# DfMUX_DAC.net
KiCad netlist of a schematic drawn in Altium Designer
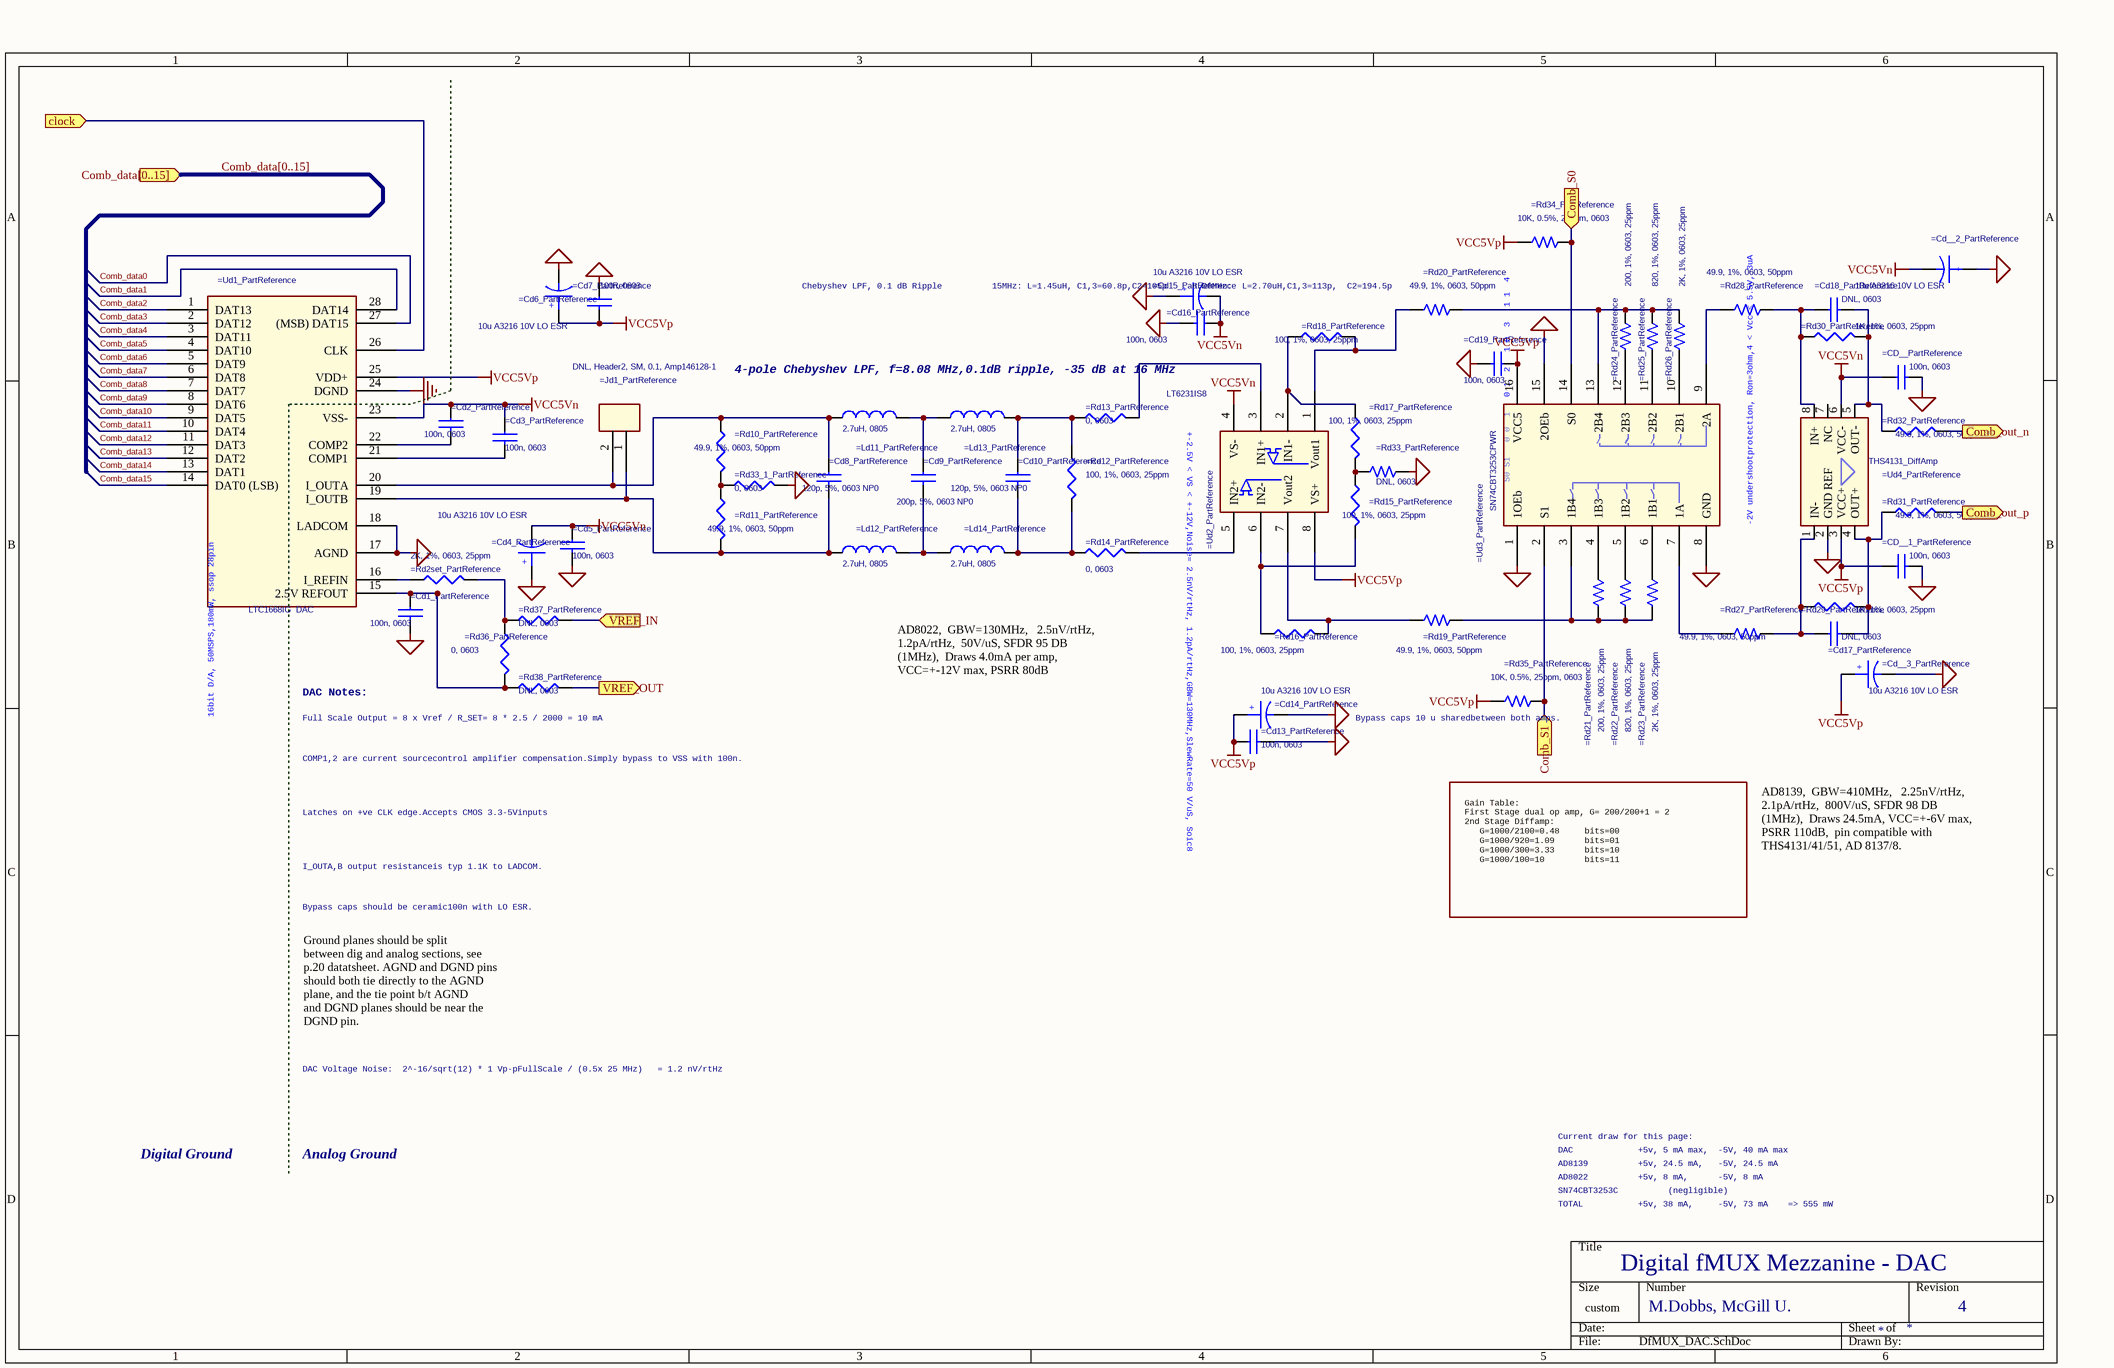
[diagram p0: DfMUX_DAC.SchDoc]

(export (version "E")
  (design (tool "Eeschema 10.0.6"))
  (components
    (comp (ref "=Cd1_PartReference")
      (value "100n, 0603")
      (footprint "0603C")
      (libsource (lib "*") (part "CAPACITOR NON-POL"))
    )
    (comp (ref "=Cd2_PartReference")
      (value "100n, 0603")
      (footprint "0603C")
      (libsource (lib "*") (part "CAPACITOR NON-POL"))
    )
    (comp (ref "=Cd3_PartReference")
      (value "100n, 0603")
      (footprint "0603C")
      (libsource (lib "*") (part "CAPACITOR NON-POL"))
    )
    (comp (ref "=Cd4_PartReference")
      (value "10u A3216 10V LO ESR")
      (libsource (lib "*") (part "CAPACITOR POL"))
    )
    (comp (ref "=Cd5_PartReference")
      (value "100n, 0603")
      (footprint "0603C")
      (libsource (lib "*") (part "CAPACITOR NON-POL"))
    )
    (comp (ref "=Cd6_PartReference")
      (value "10u A3216 10V LO ESR")
      (libsource (lib "*") (part "CAPACITOR POL"))
    )
    (comp (ref "=Cd7_PartReference")
      (value "100n, 0603")
      (footprint "0603C")
      (libsource (lib "*") (part "CAPACITOR NON-POL"))
    )
    (comp (ref "=Cd8_PartReference")
      (value "120p, 5%, 0603 NP0")
      (footprint "0603C")
      (libsource (lib "*") (part "CAPACITOR NON-POL"))
    )
    (comp (ref "=Cd9_PartReference")
      (value "200p, 5%, 0603 NP0")
      (footprint "0603C")
      (libsource (lib "*") (part "CAPACITOR NON-POL"))
    )
    (comp (ref "=Cd10_PartReference")
      (value "120p, 5%, 0603 NP0")
      (footprint "0603C")
      (libsource (lib "*") (part "CAPACITOR NON-POL"))
    )
    (comp (ref "=Cd13_PartReference")
      (value "100n, 0603")
      (footprint "0603C")
      (libsource (lib "*") (part "CAPACITOR NON-POL"))
    )
    (comp (ref "=Cd14_PartReference")
      (value "10u A3216 10V LO ESR")
      (libsource (lib "*") (part "CAPACITOR POL"))
    )
    (comp (ref "=Cd15_PartReference")
      (value "10u A3216 10V LO ESR")
      (libsource (lib "*") (part "CAPACITOR POL"))
    )
    (comp (ref "=Cd16_PartReference")
      (value "100n, 0603")
      (footprint "0603C")
      (libsource (lib "*") (part "CAPACITOR NON-POL"))
    )
    (comp (ref "=Cd17_PartReference")
      (value "DNL, 0603")
      (footprint "0603C")
      (libsource (lib "*") (part "CAPACITOR NON-POL"))
    )
    (comp (ref "=Cd18_PartReference")
      (value "DNL, 0603")
      (footprint "0603C")
      (libsource (lib "*") (part "CAPACITOR NON-POL"))
    )
    (comp (ref "=Cd19_PartReference")
      (value "100n, 0603")
      (footprint "0603C")
      (libsource (lib "*") (part "CAPACITOR NON-POL"))
    )
    (comp (ref "=CD__1_PartReference")
      (value "100n, 0603")
      (footprint "0603C")
      (libsource (lib "*") (part "CAPACITOR NON-POL"))
    )
    (comp (ref "=Cd__2_PartReference")
      (value "10u A3216 10V LO ESR")
      (libsource (lib "") (part "CAPACITOR POL_1"))
    )
    (comp (ref "=Cd__3_PartReference")
      (value "10u A3216 10V LO ESR")
      (libsource (lib "*") (part "CAPACITOR POL"))
    )
    (comp (ref "=CD__PartReference")
      (value "100n, 0603")
      (footprint "0603C")
      (libsource (lib "*") (part "CAPACITOR NON-POL"))
    )
    (comp (ref "=Jd1_PartReference")
      (value "DNL, Header2, SM, 0.1, Amp146128-1")
      (libsource (lib "*") (part "CONN_TRBLK_2"))
    )
    (comp (ref "=Ld11_PartReference") (value "2.7uH, 0805") (libsource (lib "*") (part "INDUCTOR/SM")))
    (comp (ref "=Ld12_PartReference") (value "2.7uH, 0805") (libsource (lib "*") (part "INDUCTOR/SM")))
    (comp (ref "=Ld13_PartReference") (value "2.7uH, 0805") (libsource (lib "*") (part "INDUCTOR/SM")))
    (comp (ref "=Ld14_PartReference") (value "2.7uH, 0805") (libsource (lib "*") (part "INDUCTOR/SM")))
    (comp (ref "=Rd2set_PartReference")
      (value "2K, 1%, 0603, 25ppm")
      (footprint "0603R")
      (libsource (lib "*") (part "R_Dup1"))
    )
    (comp (ref "=Rd10_PartReference")
      (value "49.9, 1%, 0603, 50ppm")
      (footprint "0603R")
      (libsource (lib "*") (part "R_Dup1"))
    )
    (comp (ref "=Rd11_PartReference")
      (value "49.9, 1%, 0603, 50ppm")
      (footprint "0603R")
      (libsource (lib "*") (part "R_Dup1"))
    )
    (comp (ref "=Rd12_PartReference")
      (value "100, 1%, 0603, 25ppm")
      (footprint "0603R")
      (libsource (lib "*") (part "R_Dup1"))
    )
    (comp (ref "=Rd13_PartReference")
      (value "0, 0603")
      (footprint "0603R")
      (libsource (lib "*") (part "R_Dup1"))
    )
    (comp (ref "=Rd14_PartReference")
      (value "0, 0603")
      (footprint "0603R")
      (libsource (lib "*") (part "R_Dup1"))
    )
    (comp (ref "=Rd15_PartReference")
      (value "100, 1%, 0603, 25ppm")
      (footprint "0603R")
      (libsource (lib "*") (part "R_Dup1"))
    )
    (comp (ref "=Rd16_PartReference")
      (value "100, 1%, 0603, 25ppm")
      (footprint "0603R")
      (libsource (lib "*") (part "R_Dup1"))
    )
    (comp (ref "=Rd17_PartReference")
      (value "100, 1%, 0603, 25ppm")
      (footprint "0603R")
      (libsource (lib "*") (part "R_Dup1"))
    )
    (comp (ref "=Rd18_PartReference")
      (value "100, 1%, 0603, 25ppm")
      (footprint "0603R")
      (libsource (lib "*") (part "R_Dup1"))
    )
    (comp (ref "=Rd19_PartReference")
      (value "49.9, 1%, 0603, 50ppm")
      (footprint "0603R")
      (libsource (lib "*") (part "R_Dup2"))
    )
    (comp (ref "=Rd20_PartReference")
      (value "49.9, 1%, 0603, 50ppm")
      (footprint "0603R")
      (libsource (lib "*") (part "R_Dup2"))
    )
    (comp (ref "=Rd21_PartReference")
      (value "200, 1%, 0603, 25ppm")
      (footprint "0603R")
      (libsource (lib "*") (part "R_Dup2"))
    )
    (comp (ref "=Rd22_PartReference")
      (value "820, 1%, 0603, 25ppm")
      (footprint "0603R")
      (libsource (lib "*") (part "R_Dup2"))
    )
    (comp (ref "=Rd23_PartReference")
      (value "2K, 1%, 0603, 25ppm")
      (footprint "0603R")
      (libsource (lib "*") (part "R_Dup2"))
    )
    (comp (ref "=Rd24_PartReference")
      (value "200, 1%, 0603, 25ppm")
      (footprint "0603R")
      (libsource (lib "*") (part "R_Dup2"))
    )
    (comp (ref "=Rd25_PartReference")
      (value "820, 1%, 0603, 25ppm")
      (footprint "0603R")
      (libsource (lib "*") (part "R_Dup2"))
    )
    (comp (ref "=Rd26_PartReference")
      (value "2K, 1%, 0603, 25ppm")
      (footprint "0603R")
      (libsource (lib "*") (part "R_Dup2"))
    )
    (comp (ref "=Rd27_PartReference")
      (value "49.9, 1%, 0603, 50ppm")
      (footprint "0603R")
      (libsource (lib "*") (part "R_Dup2"))
    )
    (comp (ref "=Rd28_PartReference")
      (value "49.9, 1%, 0603, 50ppm")
      (footprint "0603R")
      (libsource (lib "*") (part "R_Dup2"))
    )
    (comp (ref "=Rd29_PartReference")
      (value "1K, 1%, 0603, 25ppm")
      (footprint "0603R")
      (libsource (lib "*") (part "R_Dup1"))
    )
    (comp (ref "=Rd30_PartReference")
      (value "1K, 1%, 0603, 25ppm")
      (footprint "0603R")
      (libsource (lib "*") (part "R_Dup1"))
    )
    (comp (ref "=Rd31_PartReference")
      (value "49.9, 1%, 0603, 50ppm")
      (footprint "0603R")
      (libsource (lib "*") (part "R_Dup1"))
    )
    (comp (ref "=Rd32_PartReference")
      (value "49.9, 1%, 0603, 50ppm")
      (footprint "0603R")
      (libsource (lib "*") (part "R_Dup1"))
    )
    (comp (ref "=Rd33_1_PartReference")
      (value "0, 0603")
      (footprint "0603R")
      (libsource (lib "*") (part "R_Dup1"))
    )
    (comp (ref "=Rd33_PartReference")
      (value "DNL, 0603")
      (footprint "0603R")
      (libsource (lib "*") (part "R_Dup2"))
    )
    (comp (ref "=Rd34_PartReference")
      (value "10K, 0.5%, 25ppm, 0603")
      (footprint "0603R")
      (libsource (lib "*") (part "R_Dup2"))
    )
    (comp (ref "=Rd35_PartReference")
      (value "10K, 0.5%, 25ppm, 0603")
      (footprint "0603R")
      (libsource (lib "*") (part "R_Dup2"))
    )
    (comp (ref "=Rd36_PartReference")
      (value "0, 0603")
      (footprint "0603R")
      (libsource (lib "*") (part "R_Dup1"))
    )
    (comp (ref "=Rd37_PartReference")
      (value "DNL, 0603")
      (footprint "0603R")
      (libsource (lib "*") (part "R_Dup1"))
    )
    (comp (ref "=Rd38_PartReference")
      (value "DNL, 0603")
      (footprint "0603R")
      (libsource (lib "*") (part "R_Dup1"))
    )
    (comp (ref "=Ud1_PartReference") (value "LTC1668IG  DAC") (libsource (lib "*") (part "LTC1668IG  DAC")))
    (comp (ref "=Ud2_PartReference") (value "LT6231IS8") (libsource (lib "*") (part "AD8022AR_0")))
    (comp (ref "=Ud3_PartReference")
      (value "SN74CBT3253CPWR")
      (libsource (lib "*") (part "SN74CBT3253C 4MUX"))
    )
    (comp (ref "=Ud4_PartReference")
      (value "THS4131_DiffAmp")
      (libsource (lib "*") (part "THS4131_DiffAmp_0"))
    )
  )
  (nets
    (net (code "1") (name "/Comb_S0") (class "Default")
      (node (ref "=Rd34_PartReference") (pin "2") (pinfunction "2_2") (pintype "passive"))
      (node (ref "=Ud3_PartReference") (pin "14") (pinfunction "S0_14") (pintype "passive"))
    )
    (net (code "2") (name "/Comb_S1") (class "Default")
      (node (ref "=Rd35_PartReference") (pin "2") (pinfunction "2_2") (pintype "passive"))
      (node (ref "=Ud3_PartReference") (pin "2") (pinfunction "S1_2") (pintype "passive"))
    )
    (net (code "3") (name "/Comb_data0") (class "Default")
      (node (ref "=Ud1_PartReference") (pin "27") (pinfunction "(MSB)_DAT15_27") (pintype "passive"))
    )
    (net (code "4") (name "/Comb_data1") (class "Default")
      (node (ref "=Ud1_PartReference") (pin "28") (pinfunction "DAT14_28") (pintype "passive"))
    )
    (net (code "5") (name "/Comb_data2") (class "Default")
      (node (ref "=Ud1_PartReference") (pin "1") (pinfunction "DAT13_1") (pintype "passive"))
    )
    (net (code "6") (name "/Comb_data3") (class "Default")
      (node (ref "=Ud1_PartReference") (pin "2") (pinfunction "DAT12_2") (pintype "passive"))
    )
    (net (code "7") (name "/Comb_data4") (class "Default")
      (node (ref "=Ud1_PartReference") (pin "3") (pinfunction "DAT11_3") (pintype "passive"))
    )
    (net (code "8") (name "/Comb_data5") (class "Default")
      (node (ref "=Ud1_PartReference") (pin "4") (pinfunction "DAT10_4") (pintype "passive"))
    )
    (net (code "9") (name "/Comb_data6") (class "Default")
      (node (ref "=Ud1_PartReference") (pin "5") (pinfunction "DAT9_5") (pintype "passive"))
    )
    (net (code "10") (name "/Comb_data7") (class "Default")
      (node (ref "=Ud1_PartReference") (pin "6") (pinfunction "DAT8_6") (pintype "passive"))
    )
    (net (code "11") (name "/Comb_data8") (class "Default")
      (node (ref "=Ud1_PartReference") (pin "7") (pinfunction "DAT7_7") (pintype "passive"))
    )
    (net (code "12") (name "/Comb_data9") (class "Default")
      (node (ref "=Ud1_PartReference") (pin "8") (pinfunction "DAT6_8") (pintype "passive"))
    )
    (net (code "13") (name "/Comb_data10") (class "Default")
      (node (ref "=Ud1_PartReference") (pin "9") (pinfunction "DAT5_9") (pintype "passive"))
    )
    (net (code "14") (name "/Comb_data11") (class "Default")
      (node (ref "=Ud1_PartReference") (pin "10") (pinfunction "DAT4_10") (pintype "passive"))
    )
    (net (code "15") (name "/Comb_data12") (class "Default")
      (node (ref "=Ud1_PartReference") (pin "11") (pinfunction "DAT3_11") (pintype "passive"))
    )
    (net (code "16") (name "/Comb_data13") (class "Default")
      (node (ref "=Ud1_PartReference") (pin "12") (pinfunction "DAT2_12") (pintype "passive"))
    )
    (net (code "17") (name "/Comb_data14") (class "Default")
      (node (ref "=Ud1_PartReference") (pin "13") (pinfunction "DAT1_13") (pintype "passive"))
    )
    (net (code "18") (name "/Comb_data15") (class "Default")
      (node (ref "=Ud1_PartReference") (pin "14") (pinfunction "DAT0_(LSB)_14") (pintype "passive"))
    )
    (net (code "20") (name "/Comb_out_n") (class "Default")
      (node (ref "=Rd32_PartReference") (pin "2") (pinfunction "2_2") (pintype "passive"))
    )
    (net (code "21") (name "/Comb_out_p") (class "Default")
      (node (ref "=Rd31_PartReference") (pin "2") (pinfunction "2_2") (pintype "passive"))
    )
    (net (code "22") (name "/VREF_IN") (class "Default")
      (node (ref "=Rd37_PartReference") (pin "2") (pinfunction "2_2") (pintype "passive"))
    )
    (net (code "23") (name "/VREF_OUT") (class "Default")
      (node (ref "=Rd38_PartReference") (pin "2") (pinfunction "2_2") (pintype "passive"))
    )
    (net (code "24") (name "/clock") (class "Default")
      (node (ref "=Ud1_PartReference") (pin "26") (pinfunction "CLK_26") (pintype "passive"))
    )
    (net (code "25") (name "GND_DIG") (class "Default")
      (node (ref "=Ud1_PartReference") (pin "24") (pinfunction "DGND_24") (pintype "passive"))
    )
    (net (code "26") (name "GND_SIGNAL") (class "Default")
      (node (ref "=CD__1_PartReference") (pin "2") (pinfunction "2_2") (pintype "passive"))
      (node (ref "=CD__PartReference") (pin "2") (pinfunction "2_2") (pintype "passive"))
      (node (ref "=Cd13_PartReference") (pin "2") (pinfunction "2_2") (pintype "passive"))
      (node (ref "=Cd14_PartReference") (pin "2") (pinfunction "2_2") (pintype "passive"))
      (node (ref "=Cd15_PartReference") (pin "1") (pinfunction "1_1") (pintype "passive"))
      (node (ref "=Cd16_PartReference") (pin "2") (pinfunction "2_2") (pintype "passive"))
      (node (ref "=Cd19_PartReference") (pin "2") (pinfunction "2_2") (pintype "passive"))
      (node (ref "=Cd1_PartReference") (pin "2") (pinfunction "2_2") (pintype "passive"))
      (node (ref "=Cd4_PartReference") (pin "1") (pinfunction "1_1") (pintype "passive"))
      (node (ref "=Cd5_PartReference") (pin "2") (pinfunction "2_2") (pintype "passive"))
      (node (ref "=Cd6_PartReference") (pin "2") (pinfunction "2_2") (pintype "passive"))
      (node (ref "=Cd7_PartReference") (pin "1") (pinfunction "1_1") (pintype "passive"))
      (node (ref "=Cd__2_PartReference") (pin "1") (pinfunction "1_1") (pintype "passive"))
      (node (ref "=Cd__3_PartReference") (pin "2") (pinfunction "2_2") (pintype "passive"))
      (node (ref "=Rd33_1_PartReference") (pin "2") (pinfunction "2_2") (pintype "passive"))
      (node (ref "=Rd33_PartReference") (pin "2") (pinfunction "2_2") (pintype "passive"))
      (node (ref "=Ud1_PartReference") (pin "17") (pinfunction "AGND_17") (pintype "passive"))
      (node (ref "=Ud1_PartReference") (pin "18") (pinfunction "LADCOM_18") (pintype "passive"))
      (node (ref "=Ud3_PartReference") (pin "1") (pinfunction "1OEb_1") (pintype "passive"))
      (node (ref "=Ud3_PartReference") (pin "15") (pinfunction "2OEb_15") (pintype "passive"))
      (node (ref "=Ud3_PartReference") (pin "8") (pinfunction "GND_8") (pintype "passive"))
      (node (ref "=Ud4_PartReference") (pin "2") (pinfunction "GND_REF_2") (pintype "passive"))
    )
    (net (code "27") (name "Net-(=Cd9_PartReference-Pad1)") (class "Default")
      (node (ref "=Cd9_PartReference") (pin "1") (pinfunction "1_1") (pintype "passive"))
      (node (ref "=Ld11_PartReference") (pin "2") (pinfunction "2_2") (pintype "passive"))
      (node (ref "=Ld13_PartReference") (pin "1") (pinfunction "1_1") (pintype "passive"))
    )
    (net (code "28") (name "Net-(=Cd9_PartReference-Pad2)") (class "Default")
      (node (ref "=Cd9_PartReference") (pin "2") (pinfunction "2_2") (pintype "passive"))
      (node (ref "=Ld12_PartReference") (pin "2") (pinfunction "2_2") (pintype "passive"))
      (node (ref "=Ld14_PartReference") (pin "1") (pinfunction "1_1") (pintype "passive"))
    )
    (net (code "29") (name "Net-(=Cd10_PartReference-Pad1)") (class "Default")
      (node (ref "=Cd10_PartReference") (pin "1") (pinfunction "1_1") (pintype "passive"))
      (node (ref "=Ld13_PartReference") (pin "2") (pinfunction "2_2") (pintype "passive"))
      (node (ref "=Rd12_PartReference") (pin "1") (pinfunction "1_1") (pintype "passive"))
      (node (ref "=Rd13_PartReference") (pin "1") (pinfunction "1_1") (pintype "passive"))
    )
    (net (code "30") (name "Net-(=Cd10_PartReference-Pad2)") (class "Default")
      (node (ref "=Cd10_PartReference") (pin "2") (pinfunction "2_2") (pintype "passive"))
      (node (ref "=Ld14_PartReference") (pin "2") (pinfunction "2_2") (pintype "passive"))
      (node (ref "=Rd12_PartReference") (pin "2") (pinfunction "2_2") (pintype "passive"))
      (node (ref "=Rd14_PartReference") (pin "1") (pinfunction "1_1") (pintype "passive"))
    )
    (net (code "31") (name "Net-(=Rd2set_PartReference-Pad2)") (class "Default")
      (node (ref "=Rd2set_PartReference") (pin "2") (pinfunction "2_2") (pintype "passive"))
      (node (ref "=Rd36_PartReference") (pin "1") (pinfunction "1_1") (pintype "passive"))
      (node (ref "=Rd37_PartReference") (pin "1") (pinfunction "1_1") (pintype "passive"))
    )
    (net (code "32") (name "Net-(=Rd10_PartReference-Pad2)") (class "Default")
      (node (ref "=Rd10_PartReference") (pin "2") (pinfunction "2_2") (pintype "passive"))
      (node (ref "=Rd11_PartReference") (pin "1") (pinfunction "1_1") (pintype "passive"))
      (node (ref "=Rd33_1_PartReference") (pin "1") (pinfunction "1_1") (pintype "passive"))
    )
    (net (code "33") (name "Net-(=Rd15_PartReference-Pad1)") (class "Default")
      (node (ref "=Rd15_PartReference") (pin "1") (pinfunction "1_1") (pintype "passive"))
      (node (ref "=Rd17_PartReference") (pin "2") (pinfunction "2_2") (pintype "passive"))
      (node (ref "=Rd33_PartReference") (pin "1") (pinfunction "1_1") (pintype "passive"))
    )
    (net (code "34") (name "Net-(=Ud1_PartReference-2.5V_REFOUT)") (class "Default")
      (node (ref "=Cd1_PartReference") (pin "1") (pinfunction "1_1") (pintype "passive"))
      (node (ref "=Rd36_PartReference") (pin "2") (pinfunction "2_2") (pintype "passive"))
      (node (ref "=Rd38_PartReference") (pin "1") (pinfunction "1_1") (pintype "passive"))
      (node (ref "=Ud1_PartReference") (pin "15") (pinfunction "2.5V_REFOUT_15") (pintype "passive"))
    )
    (net (code "35") (name "Net-(=Ud1_PartReference-COMP1)") (class "Default")
      (node (ref "=Cd3_PartReference") (pin "2") (pinfunction "2_2") (pintype "passive"))
      (node (ref "=Ud1_PartReference") (pin "21") (pinfunction "COMP1_21") (pintype "passive"))
    )
    (net (code "36") (name "Net-(=Ud1_PartReference-COMP2)") (class "Default")
      (node (ref "=Cd2_PartReference") (pin "2") (pinfunction "2_2") (pintype "passive"))
      (node (ref "=Ud1_PartReference") (pin "22") (pinfunction "COMP2_22") (pintype "passive"))
    )
    (net (code "37") (name "Net-(=Ud1_PartReference-I_OUTA)") (class "Default")
      (node (ref "=Cd8_PartReference") (pin "1") (pinfunction "1_1") (pintype "passive"))
      (node (ref "=Jd1_PartReference") (pin "2") (pinfunction "2_2") (pintype "passive"))
      (node (ref "=Ld11_PartReference") (pin "1") (pinfunction "1_1") (pintype "passive"))
      (node (ref "=Rd10_PartReference") (pin "1") (pinfunction "1_1") (pintype "passive"))
      (node (ref "=Ud1_PartReference") (pin "20") (pinfunction "I_OUTA_20") (pintype "passive"))
    )
    (net (code "38") (name "Net-(=Ud1_PartReference-I_OUTB)") (class "Default")
      (node (ref "=Cd8_PartReference") (pin "2") (pinfunction "2_2") (pintype "passive"))
      (node (ref "=Jd1_PartReference") (pin "1") (pinfunction "1_1") (pintype "passive"))
      (node (ref "=Ld12_PartReference") (pin "1") (pinfunction "1_1") (pintype "passive"))
      (node (ref "=Rd11_PartReference") (pin "2") (pinfunction "2_2") (pintype "passive"))
      (node (ref "=Ud1_PartReference") (pin "19") (pinfunction "I_OUTB_19") (pintype "passive"))
    )
    (net (code "39") (name "Net-(=Ud1_PartReference-I_REFIN)") (class "Default")
      (node (ref "=Rd2set_PartReference") (pin "1") (pinfunction "1_1") (pintype "passive"))
      (node (ref "=Ud1_PartReference") (pin "16") (pinfunction "I_REFIN_16") (pintype "passive"))
    )
    (net (code "40") (name "Net-(=Ud2_PartReference-IN1+)") (class "Default")
      (node (ref "=Rd13_PartReference") (pin "2") (pinfunction "2_2") (pintype "passive"))
      (node (ref "=Ud2_PartReference") (pin "3") (pinfunction "IN1+_3") (pintype "passive"))
    )
    (net (code "41") (name "Net-(=Ud2_PartReference-IN1-)") (class "Default")
      (node (ref "=Rd17_PartReference") (pin "1") (pinfunction "1_1") (pintype "passive"))
      (node (ref "=Rd18_PartReference") (pin "1") (pinfunction "1_1") (pintype "passive"))
      (node (ref "=Ud2_PartReference") (pin "2") (pinfunction "IN1-_2") (pintype "passive"))
    )
    (net (code "42") (name "Net-(=Ud2_PartReference-IN2+)") (class "Default")
      (node (ref "=Rd14_PartReference") (pin "2") (pinfunction "2_2") (pintype "passive"))
      (node (ref "=Ud2_PartReference") (pin "5") (pinfunction "IN2+_5") (pintype "passive"))
    )
    (net (code "43") (name "Net-(=Ud2_PartReference-IN2-)") (class "Default")
      (node (ref "=Rd15_PartReference") (pin "2") (pinfunction "2_2") (pintype "passive"))
      (node (ref "=Rd16_PartReference") (pin "1") (pinfunction "1_1") (pintype "passive"))
      (node (ref "=Ud2_PartReference") (pin "6") (pinfunction "IN2-_6") (pintype "passive"))
    )
    (net (code "44") (name "Net-(=Ud2_PartReference-Vout1)") (class "Default")
      (node (ref "=Rd18_PartReference") (pin "2") (pinfunction "2_2") (pintype "passive"))
      (node (ref "=Rd20_PartReference") (pin "1") (pinfunction "1_1") (pintype "passive"))
      (node (ref "=Ud2_PartReference") (pin "1") (pinfunction "Vout1_1") (pintype "passive"))
    )
    (net (code "45") (name "Net-(=Ud2_PartReference-Vout2)") (class "Default")
      (node (ref "=Rd16_PartReference") (pin "2") (pinfunction "2_2") (pintype "passive"))
      (node (ref "=Rd19_PartReference") (pin "1") (pinfunction "1_1") (pintype "passive"))
      (node (ref "=Ud2_PartReference") (pin "7") (pinfunction "Vout2_7") (pintype "passive"))
    )
    (net (code "46") (name "Net-(=Ud3_PartReference-1A)") (class "Default")
      (node (ref "=Rd27_PartReference") (pin "1") (pinfunction "1_1") (pintype "passive"))
      (node (ref "=Ud3_PartReference") (pin "7") (pinfunction "1A_7") (pintype "passive"))
    )
    (net (code "47") (name "Net-(=Ud3_PartReference-1B1)") (class "Default")
      (node (ref "=Rd23_PartReference") (pin "2") (pinfunction "2_2") (pintype "passive"))
      (node (ref "=Ud3_PartReference") (pin "6") (pinfunction "1B1_6") (pintype "passive"))
    )
    (net (code "48") (name "Net-(=Ud3_PartReference-1B2)") (class "Default")
      (node (ref "=Rd22_PartReference") (pin "2") (pinfunction "2_2") (pintype "passive"))
      (node (ref "=Ud3_PartReference") (pin "5") (pinfunction "1B2_5") (pintype "passive"))
    )
    (net (code "49") (name "Net-(=Ud3_PartReference-1B3)") (class "Default")
      (node (ref "=Rd21_PartReference") (pin "2") (pinfunction "2_2") (pintype "passive"))
      (node (ref "=Ud3_PartReference") (pin "4") (pinfunction "1B3_4") (pintype "passive"))
    )
    (net (code "50") (name "Net-(=Ud3_PartReference-1B4)") (class "Default")
      (node (ref "=Rd19_PartReference") (pin "2") (pinfunction "2_2") (pintype "passive"))
      (node (ref "=Rd21_PartReference") (pin "1") (pinfunction "1_1") (pintype "passive"))
      (node (ref "=Rd22_PartReference") (pin "1") (pinfunction "1_1") (pintype "passive"))
      (node (ref "=Rd23_PartReference") (pin "1") (pinfunction "1_1") (pintype "passive"))
      (node (ref "=Ud3_PartReference") (pin "3") (pinfunction "1B4_3") (pintype "passive"))
    )
    (net (code "51") (name "Net-(=Ud3_PartReference-2A)") (class "Default")
      (node (ref "=Rd28_PartReference") (pin "1") (pinfunction "1_1") (pintype "passive"))
      (node (ref "=Ud3_PartReference") (pin "9") (pinfunction "2A_9") (pintype "passive"))
    )
    (net (code "52") (name "Net-(=Ud3_PartReference-2B1)") (class "Default")
      (node (ref "=Rd26_PartReference") (pin "1") (pinfunction "1_1") (pintype "passive"))
      (node (ref "=Ud3_PartReference") (pin "10") (pinfunction "2B1_10") (pintype "passive"))
    )
    (net (code "53") (name "Net-(=Ud3_PartReference-2B2)") (class "Default")
      (node (ref "=Rd25_PartReference") (pin "1") (pinfunction "1_1") (pintype "passive"))
      (node (ref "=Ud3_PartReference") (pin "11") (pinfunction "2B2_11") (pintype "passive"))
    )
    (net (code "54") (name "Net-(=Ud3_PartReference-2B3)") (class "Default")
      (node (ref "=Rd24_PartReference") (pin "1") (pinfunction "1_1") (pintype "passive"))
      (node (ref "=Ud3_PartReference") (pin "12") (pinfunction "2B3_12") (pintype "passive"))
    )
    (net (code "55") (name "Net-(=Ud3_PartReference-2B4)") (class "Default")
      (node (ref "=Rd20_PartReference") (pin "2") (pinfunction "2_2") (pintype "passive"))
      (node (ref "=Rd24_PartReference") (pin "2") (pinfunction "2_2") (pintype "passive"))
      (node (ref "=Rd25_PartReference") (pin "2") (pinfunction "2_2") (pintype "passive"))
      (node (ref "=Rd26_PartReference") (pin "2") (pinfunction "2_2") (pintype "passive"))
      (node (ref "=Ud3_PartReference") (pin "13") (pinfunction "2B4_13") (pintype "passive"))
    )
    (net (code "56") (name "Net-(=Ud4_PartReference-IN+)") (class "Default")
      (node (ref "=Cd18_PartReference") (pin "1") (pinfunction "1_1") (pintype "passive"))
      (node (ref "=Rd28_PartReference") (pin "2") (pinfunction "2_2") (pintype "passive"))
      (node (ref "=Rd30_PartReference") (pin "1") (pinfunction "1_1") (pintype "passive"))
      (node (ref "=Ud4_PartReference") (pin "8") (pinfunction "IN+_8") (pintype "passive"))
    )
    (net (code "57") (name "Net-(=Ud4_PartReference-IN-)") (class "Default")
      (node (ref "=Cd17_PartReference") (pin "1") (pinfunction "1_1") (pintype "passive"))
      (node (ref "=Rd27_PartReference") (pin "2") (pinfunction "2_2") (pintype "passive"))
      (node (ref "=Rd29_PartReference") (pin "1") (pinfunction "1_1") (pintype "passive"))
      (node (ref "=Ud4_PartReference") (pin "1") (pinfunction "IN-_1") (pintype "passive"))
    )
    (net (code "58") (name "Net-(=Ud4_PartReference-OUT+)") (class "Default")
      (node (ref "=Cd17_PartReference") (pin "2") (pinfunction "2_2") (pintype "passive"))
      (node (ref "=Rd29_PartReference") (pin "2") (pinfunction "2_2") (pintype "passive"))
      (node (ref "=Rd31_PartReference") (pin "1") (pinfunction "1_1") (pintype "passive"))
      (node (ref "=Ud4_PartReference") (pin "4") (pinfunction "OUT+_4") (pintype "passive"))
    )
    (net (code "59") (name "Net-(=Ud4_PartReference-OUT-)") (class "Default")
      (node (ref "=Cd18_PartReference") (pin "2") (pinfunction "2_2") (pintype "passive"))
      (node (ref "=Rd30_PartReference") (pin "2") (pinfunction "2_2") (pintype "passive"))
      (node (ref "=Rd32_PartReference") (pin "1") (pinfunction "1_1") (pintype "passive"))
      (node (ref "=Ud4_PartReference") (pin "5") (pinfunction "OUT-_5") (pintype "passive"))
    )
    (net (code "60") (name "VCC5Vn") (class "Default")
      (node (ref "=CD__PartReference") (pin "1") (pinfunction "1_1") (pintype "passive"))
      (node (ref "=Cd15_PartReference") (pin "2") (pinfunction "2_2") (pintype "passive"))
      (node (ref "=Cd16_PartReference") (pin "1") (pinfunction "1_1") (pintype "passive"))
      (node (ref "=Cd2_PartReference") (pin "1") (pinfunction "1_1") (pintype "passive"))
      (node (ref "=Cd3_PartReference") (pin "1") (pinfunction "1_1") (pintype "passive"))
      (node (ref "=Cd4_PartReference") (pin "2") (pinfunction "2_2") (pintype "passive"))
      (node (ref "=Cd5_PartReference") (pin "1") (pinfunction "1_1") (pintype "passive"))
      (node (ref "=Cd__2_PartReference") (pin "2") (pinfunction "2_2") (pintype "passive"))
      (node (ref "=Ud1_PartReference") (pin "23") (pinfunction "VSS-_23") (pintype "passive"))
      (node (ref "=Ud2_PartReference") (pin "4") (pinfunction "VS-_4") (pintype "passive"))
      (node (ref "=Ud4_PartReference") (pin "6") (pinfunction "VCC-_6") (pintype "passive"))
    )
    (net (code "61") (name "VCC5Vp") (class "Default")
      (node (ref "=CD__1_PartReference") (pin "1") (pinfunction "1_1") (pintype "passive"))
      (node (ref "=Cd13_PartReference") (pin "1") (pinfunction "1_1") (pintype "passive"))
      (node (ref "=Cd14_PartReference") (pin "1") (pinfunction "1_1") (pintype "passive"))
      (node (ref "=Cd19_PartReference") (pin "1") (pinfunction "1_1") (pintype "passive"))
      (node (ref "=Cd6_PartReference") (pin "1") (pinfunction "1_1") (pintype "passive"))
      (node (ref "=Cd7_PartReference") (pin "2") (pinfunction "2_2") (pintype "passive"))
      (node (ref "=Cd__3_PartReference") (pin "1") (pinfunction "1_1") (pintype "passive"))
      (node (ref "=Rd34_PartReference") (pin "1") (pinfunction "1_1") (pintype "passive"))
      (node (ref "=Rd35_PartReference") (pin "1") (pinfunction "1_1") (pintype "passive"))
      (node (ref "=Ud1_PartReference") (pin "25") (pinfunction "VDD+_25") (pintype "passive"))
      (node (ref "=Ud2_PartReference") (pin "8") (pinfunction "VS+_8") (pintype "passive"))
      (node (ref "=Ud3_PartReference") (pin "16") (pinfunction "VCC5_16") (pintype "passive"))
      (node (ref "=Ud4_PartReference") (pin "3") (pinfunction "VCC+_3") (pintype "passive"))
    )
    (net (code "62") (name "unconnected-(=Ud4_PartReference-NC-Pad7)") (class "Default")
      (node (ref "=Ud4_PartReference") (pin "7") (pinfunction "NC_7") (pintype "passive"))
    )
  )
)
